# nand_mit_compatibility.net
KiCad netlist of a schematic drawn in EAGLE
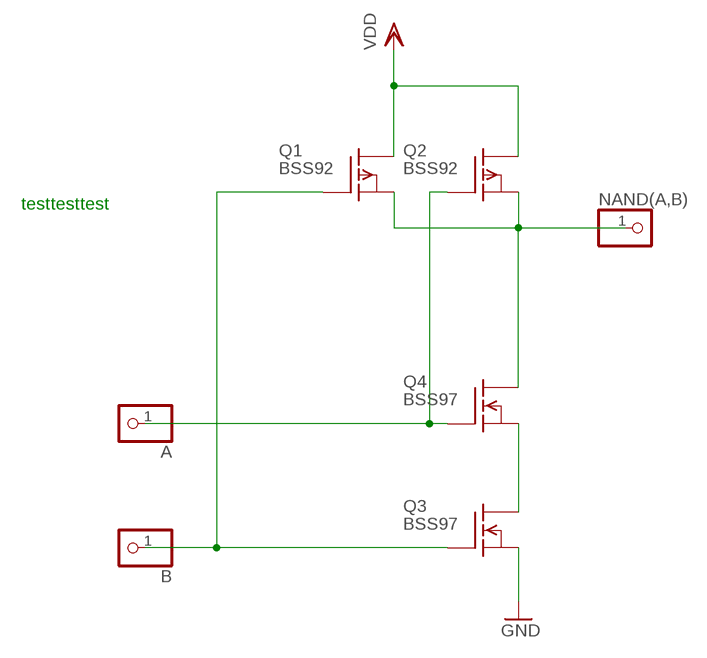
[diagram p0: schematic, sheet 1]

(export (version "E")
  (design (tool "Eeschema 10.0.6"))
  (components
    (comp (ref "A")
      (value "PINHD-1X1")
      (footprint "eagle-import:1X01")
      (libsource (lib "eagle-import") (part "PINHD-1X1"))
    )
    (comp (ref "B")
      (value "PINHD-1X1")
      (footprint "eagle-import:1X01")
      (libsource (lib "eagle-import") (part "PINHD-1X1"))
    )
    (comp (ref "NAND(A,B)")
      (value "PINHD-1X1")
      (footprint "eagle-import:1X01")
      (libsource (lib "eagle-import") (part "PINHD-1X1"))
    )
    (comp (ref "Q1")
      (value "BSS92")
      (footprint "eagle-import:TO92")
      (libsource (lib "eagle-import") (part "BSS92"))
    )
    (comp (ref "Q2")
      (value "BSS92")
      (footprint "eagle-import:TO92")
      (libsource (lib "eagle-import") (part "BSS92"))
    )
    (comp (ref "Q3")
      (value "BSS97")
      (footprint "eagle-import:TO202")
      (libsource (lib "eagle-import") (part "BSS97"))
    )
    (comp (ref "Q4")
      (value "BSS97")
      (footprint "eagle-import:TO202")
      (libsource (lib "eagle-import") (part "BSS97"))
    )
  )
  (nets
    (net (code "1") (name "GND") (class "Default")
      (node (ref "Q3") (pin "1") (pinfunction "S_1") (pintype "passive"))
    )
    (net (code "2") (name "Net-(Q1-G)") (class "Default")
      (node (ref "B") (pin "1") (pinfunction "1_1") (pintype "passive"))
      (node (ref "Q1") (pin "1") (pinfunction "G_1") (pintype "passive"))
      (node (ref "Q3") (pin "3") (pinfunction "G_3") (pintype "passive"))
    )
    (net (code "3") (name "Net-(Q1-S)") (class "Default")
      (node (ref "NAND(A,B)") (pin "1") (pinfunction "1_1") (pintype "passive"))
      (node (ref "Q1") (pin "3") (pinfunction "S_3") (pintype "passive"))
      (node (ref "Q2") (pin "3") (pinfunction "S_3") (pintype "passive"))
      (node (ref "Q4") (pin "2") (pinfunction "D_2") (pintype "passive"))
    )
    (net (code "4") (name "Net-(Q2-G)") (class "Default")
      (node (ref "A") (pin "1") (pinfunction "1_1") (pintype "passive"))
      (node (ref "Q2") (pin "1") (pinfunction "G_1") (pintype "passive"))
      (node (ref "Q4") (pin "3") (pinfunction "G_3") (pintype "passive"))
    )
    (net (code "5") (name "Net-(Q3-D)") (class "Default")
      (node (ref "Q3") (pin "2") (pinfunction "D_2") (pintype "passive"))
      (node (ref "Q4") (pin "1") (pinfunction "S_1") (pintype "passive"))
    )
    (net (code "6") (name "VDD") (class "Default")
      (node (ref "Q1") (pin "2") (pinfunction "D_2") (pintype "passive"))
      (node (ref "Q2") (pin "2") (pinfunction "D_2") (pintype "passive"))
    )
  )
)
